# Adafruit_SPI_Flash_SD_Card.net
KiCad netlist of a schematic drawn in EAGLE
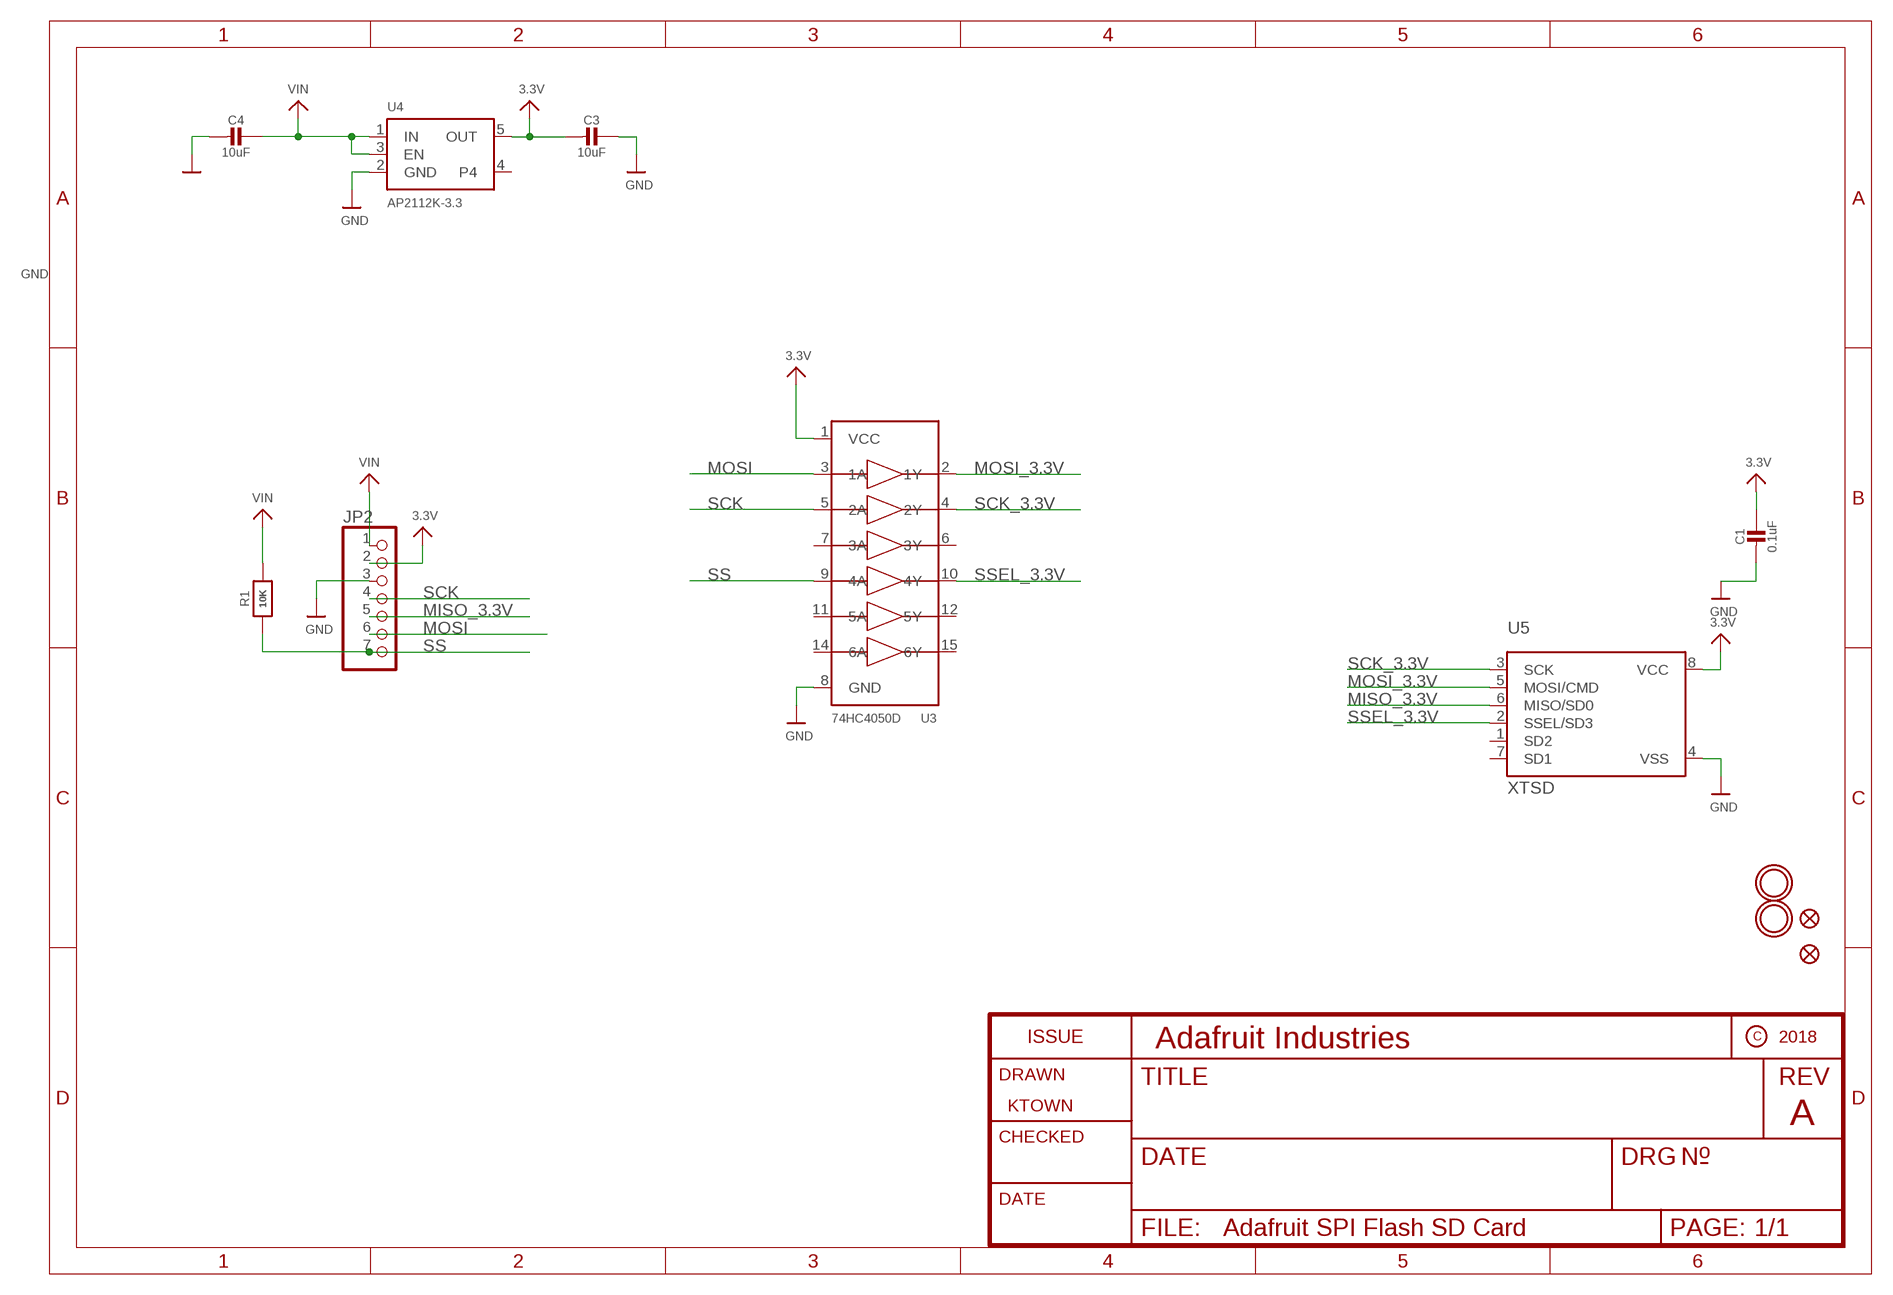
[diagram p0: schematic, sheet 1]

(export (version "E")
  (design (tool "Eeschema 10.0.6"))
  (components
    (comp (ref "C1")
      (value "0.1uF")
      (footprint "eagle-import:0603-NO")
      (libsource (lib "eagle-import") (part "CAP_CERAMIC0603_NO"))
    )
    (comp (ref "C3")
      (value "10uF")
      (footprint "eagle-import:0805-NO")
      (libsource (lib "eagle-import") (part "CAP_CERAMIC0805-NOOUTLINE"))
    )
    (comp (ref "C4")
      (value "10uF")
      (footprint "eagle-import:0805-NO")
      (libsource (lib "eagle-import") (part "CAP_CERAMIC0805-NOOUTLINE"))
    )
    (comp (ref "FID2")
      (value "FIDUCIAL_1MM")
      (footprint "eagle-import:FIDUCIAL_1MM")
      (libsource (lib "eagle-import") (part "FIDUCIAL_1MM"))
    )
    (comp (ref "FID3")
      (value "FIDUCIAL_1MM")
      (footprint "eagle-import:FIDUCIAL_1MM")
      (libsource (lib "eagle-import") (part "FIDUCIAL_1MM"))
    )
    (comp (ref "JP2")
      (value "HEADER-1X770MIL")
      (footprint "eagle-import:1X07_ROUND_70")
      (libsource (lib "eagle-import") (part "HEADER-1X770MIL"))
    )
    (comp (ref "R1")
      (value "10K")
      (footprint "eagle-import:0603-NO")
      (libsource (lib "eagle-import") (part "RESISTOR_0603_NOOUT"))
    )
    (comp (ref "U$16")
      (value "MOUNTINGHOLE2.5")
      (footprint "eagle-import:MOUNTINGHOLE_2.5_PLATED")
      (libsource (lib "eagle-import") (part "MOUNTINGHOLE2.5"))
    )
    (comp (ref "U$17")
      (value "MOUNTINGHOLE2.5")
      (footprint "eagle-import:MOUNTINGHOLE_2.5_PLATED")
      (libsource (lib "eagle-import") (part "MOUNTINGHOLE2.5"))
    )
    (comp (ref "U3")
      (value "74HC4050D")
      (footprint "eagle-import:TSSOP16")
      (libsource (lib "eagle-import") (part "74HC4050DTSSOP"))
    )
    (comp (ref "U4")
      (value "AP2112K-3.3")
      (footprint "eagle-import:SOT23-5")
      (libsource (lib "eagle-import") (part "VREG_SOT23-5"))
    )
    (comp (ref "U5")
      (value "XTSD")
      (footprint "eagle-import:LGA8_8X6")
      (libsource (lib "eagle-import") (part "SMT_SDCARD_8PIN"))
    )
  )
  (nets
    (net (code "1") (name "/MISO_3.3V") (class "Default")
      (node (ref "JP2") (pin "5") (pinfunction "5_5") (pintype "passive"))
      (node (ref "U5") (pin "6") (pinfunction "MISO/SD0_6") (pintype "bidirectional"))
    )
    (net (code "2") (name "/MOSI") (class "Default")
      (node (ref "JP2") (pin "6") (pinfunction "6_6") (pintype "passive"))
      (node (ref "U3") (pin "3") (pinfunction "1A_3") (pintype "bidirectional"))
    )
    (net (code "3") (name "/MOSI_3.3V") (class "Default")
      (node (ref "U3") (pin "2") (pinfunction "1Y_2") (pintype "bidirectional"))
      (node (ref "U5") (pin "5") (pinfunction "MOSI/CMD_5") (pintype "bidirectional"))
    )
    (net (code "4") (name "/SCK") (class "Default")
      (node (ref "JP2") (pin "4") (pinfunction "4_4") (pintype "passive"))
      (node (ref "U3") (pin "5") (pinfunction "2A_5") (pintype "bidirectional"))
    )
    (net (code "5") (name "/SCK_3.3V") (class "Default")
      (node (ref "U3") (pin "4") (pinfunction "2Y_4") (pintype "bidirectional"))
      (node (ref "U5") (pin "3") (pinfunction "SCK_3") (pintype "input"))
    )
    (net (code "6") (name "/SS") (class "Default")
      (node (ref "JP2") (pin "7") (pinfunction "7_7") (pintype "passive"))
      (node (ref "R1") (pin "1") (pinfunction "1_1") (pintype "passive"))
      (node (ref "U3") (pin "9") (pinfunction "4A_9") (pintype "bidirectional"))
    )
    (net (code "7") (name "/SSEL_3.3V") (class "Default")
      (node (ref "U3") (pin "10") (pinfunction "4Y_10") (pintype "bidirectional"))
      (node (ref "U5") (pin "2") (pinfunction "SSEL/SD3_2") (pintype "bidirectional"))
    )
    (net (code "8") (name "3.3V") (class "Default")
      (node (ref "C1") (pin "1") (pinfunction "1_1") (pintype "passive"))
      (node (ref "C3") (pin "2") (pinfunction "2_2") (pintype "passive"))
      (node (ref "JP2") (pin "2") (pinfunction "2_2") (pintype "passive"))
      (node (ref "U3") (pin "1") (pinfunction "VCC_1") (pintype "bidirectional"))
      (node (ref "U4") (pin "5") (pinfunction "OUT_5") (pintype "power_in"))
      (node (ref "U5") (pin "8") (pinfunction "VCC_8") (pintype "power_in"))
    )
    (net (code "9") (name "GND") (class "Default")
      (node (ref "C1") (pin "2") (pinfunction "2_2") (pintype "passive"))
      (node (ref "C3") (pin "1") (pinfunction "1_1") (pintype "passive"))
      (node (ref "C4") (pin "2") (pinfunction "2_2") (pintype "passive"))
      (node (ref "JP2") (pin "3") (pinfunction "3_3") (pintype "passive"))
      (node (ref "U3") (pin "8") (pinfunction "GND_8") (pintype "bidirectional"))
      (node (ref "U4") (pin "2") (pinfunction "GND_2") (pintype "power_in"))
      (node (ref "U5") (pin "4") (pinfunction "VSS_4") (pintype "power_in"))
    )
    (net (code "10") (name "VIN") (class "Default")
      (node (ref "C4") (pin "1") (pinfunction "1_1") (pintype "passive"))
      (node (ref "JP2") (pin "1") (pinfunction "1_1") (pintype "passive"))
      (node (ref "R1") (pin "2") (pinfunction "2_2") (pintype "passive"))
      (node (ref "U4") (pin "1") (pinfunction "IN_1") (pintype "power_in"))
      (node (ref "U4") (pin "3") (pinfunction "EN_3") (pintype "input"))
    )
    (net (code "11") (name "unconnected-(U3-3A-Pad7)") (class "Default")
      (node (ref "U3") (pin "7") (pinfunction "3A_7") (pintype "bidirectional"))
    )
    (net (code "12") (name "unconnected-(U3-3Y-Pad6)") (class "Default")
      (node (ref "U3") (pin "6") (pinfunction "3Y_6") (pintype "bidirectional"))
    )
    (net (code "13") (name "unconnected-(U3-5A-Pad11)") (class "Default")
      (node (ref "U3") (pin "11") (pinfunction "5A_11") (pintype "bidirectional"))
    )
    (net (code "14") (name "unconnected-(U3-5Y-Pad12)") (class "Default")
      (node (ref "U3") (pin "12") (pinfunction "5Y_12") (pintype "bidirectional"))
    )
    (net (code "15") (name "unconnected-(U3-6A-Pad14)") (class "Default")
      (node (ref "U3") (pin "14") (pinfunction "6A_14") (pintype "bidirectional"))
    )
    (net (code "16") (name "unconnected-(U3-6Y-Pad15)") (class "Default")
      (node (ref "U3") (pin "15") (pinfunction "6Y_15") (pintype "bidirectional"))
    )
    (net (code "17") (name "unconnected-(U4-P4-Pad4)") (class "Default")
      (node (ref "U4") (pin "4") (pinfunction "P4_4") (pintype "bidirectional"))
    )
    (net (code "18") (name "unconnected-(U5-SD1-Pad7)") (class "Default")
      (node (ref "U5") (pin "7") (pinfunction "SD1_7") (pintype "bidirectional"))
    )
    (net (code "19") (name "unconnected-(U5-SD2-Pad1)") (class "Default")
      (node (ref "U5") (pin "1") (pinfunction "SD2_1") (pintype "bidirectional"))
    )
  )
)
